# LOW_CURR_MOS.net
KiCad netlist of a schematic drawn in Altium Designer
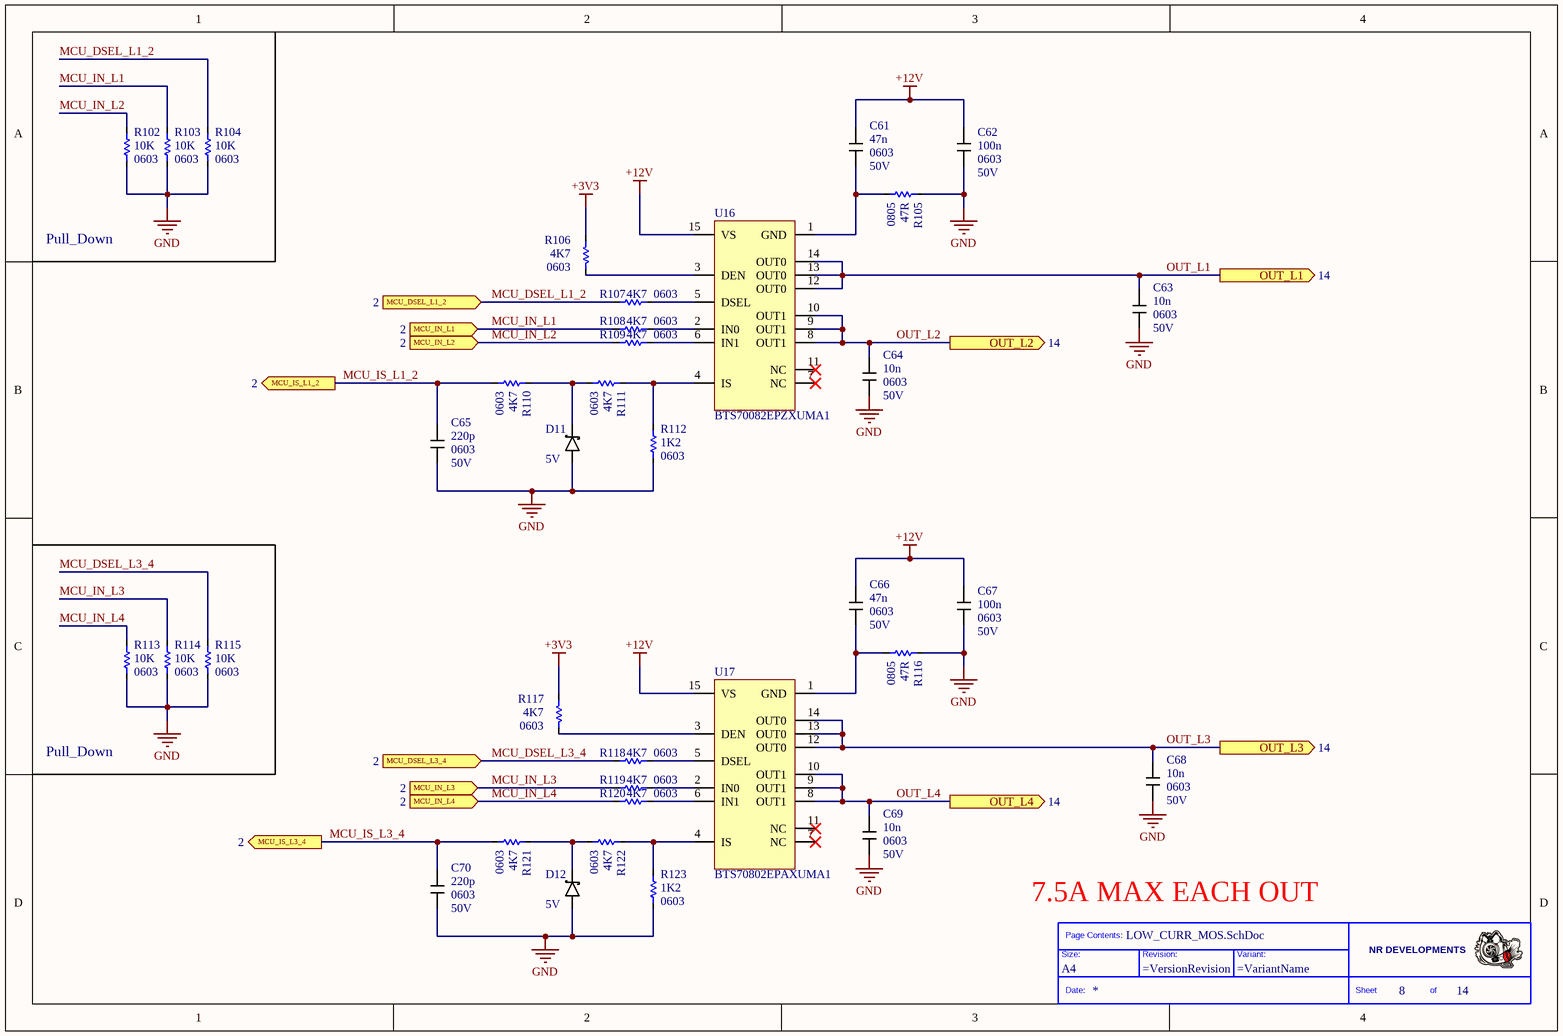
[diagram p0: LOW_CURR_MOS.SchDoc]

(export (version "E")
  (design (tool "Eeschema 10.0.6"))
  (components
    (comp (ref "C61")
      (value "47n")
      (footprint "CAPC1608X09M")
      (fields
        (field (name "MANUFACTURER") "KEMET")
        (field (name "PARTNUMBER") "C0603C473M5RACTU")
        (field (name "CASE") "0603")
        (field (name "VOLTAGE") "50V")
        (field (name "Comment") "CAP")
      )
      (libsource (lib "My_LIB") (part "CAP"))
    )
    (comp (ref "C62")
      (value "100n")
      (footprint "CAPC1608X09M")
      (fields
        (field (name "CASE") "0603")
        (field (name "VOLTAGE") "50V")
        (field (name "MANUFACTURER") "KEMET")
        (field (name "PARTNUMBER") "C0603C104K5RACTU")
        (field (name "Comment") "CAP")
      )
      (libsource (lib "My_LIB") (part "CAP"))
    )
    (comp (ref "C63")
      (value "10n")
      (footprint "CAPC1608X09M")
      (fields
        (field (name "MANUFACTURER") "KEMET")
        (field (name "PARTNUMBER") "C0603C103M5RACTM")
        (field (name "CASE") "0603")
        (field (name "VOLTAGE") "50V")
        (field (name "Comment") "CAP")
      )
      (libsource (lib "My_LIB") (part "CAP"))
    )
    (comp (ref "C64")
      (value "10n")
      (footprint "CAPC1608X09M")
      (fields
        (field (name "MANUFACTURER") "KEMET")
        (field (name "PARTNUMBER") "C0603C103M5RACTM")
        (field (name "CASE") "0603")
        (field (name "VOLTAGE") "50V")
        (field (name "Comment") "CAP")
      )
      (libsource (lib "My_LIB") (part "CAP"))
    )
    (comp (ref "C65")
      (value "220p")
      (footprint "CAPC1608X09M")
      (fields
        (field (name "MANUFACTURER") "KEMET")
        (field (name "PARTNUMBER") "C0603C221J5RACTU")
        (field (name "CASE") "0603")
        (field (name "VOLTAGE") "50V")
        (field (name "Comment") "CAP")
      )
      (libsource (lib "My_LIB") (part "CAP"))
    )
    (comp (ref "C66")
      (value "47n")
      (footprint "CAPC1608X09M")
      (fields
        (field (name "MANUFACTURER") "KEMET")
        (field (name "PARTNUMBER") "C0603C473M5RACTU")
        (field (name "CASE") "0603")
        (field (name "VOLTAGE") "50V")
        (field (name "Comment") "CAP")
      )
      (libsource (lib "My_LIB") (part "CAP"))
    )
    (comp (ref "C67")
      (value "100n")
      (footprint "CAPC1608X09M")
      (fields
        (field (name "CASE") "0603")
        (field (name "VOLTAGE") "50V")
        (field (name "MANUFACTURER") "KEMET")
        (field (name "PARTNUMBER") "C0603C104K5RACTU")
        (field (name "Comment") "CAP")
      )
      (libsource (lib "My_LIB") (part "CAP"))
    )
    (comp (ref "C68")
      (value "10n")
      (footprint "CAPC1608X09M")
      (fields
        (field (name "MANUFACTURER") "KEMET")
        (field (name "PARTNUMBER") "C0603C103M5RACTM")
        (field (name "CASE") "0603")
        (field (name "VOLTAGE") "50V")
        (field (name "Comment") "CAP")
      )
      (libsource (lib "My_LIB") (part "CAP"))
    )
    (comp (ref "C69")
      (value "10n")
      (footprint "CAPC1608X09M")
      (fields
        (field (name "MANUFACTURER") "KEMET")
        (field (name "PARTNUMBER") "C0603C103M5RACTM")
        (field (name "CASE") "0603")
        (field (name "VOLTAGE") "50V")
        (field (name "Comment") "CAP")
      )
      (libsource (lib "My_LIB") (part "CAP"))
    )
    (comp (ref "C70")
      (value "220p")
      (footprint "CAPC1608X09M")
      (fields
        (field (name "MANUFACTURER") "KEMET")
        (field (name "PARTNUMBER") "C0603C221J5RACTU")
        (field (name "CASE") "0603")
        (field (name "VOLTAGE") "50V")
        (field (name "Comment") "CAP")
      )
      (libsource (lib "My_LIB") (part "CAP"))
    )
    (comp (ref "D11")
      (value "5V")
      (footprint "SOT65P210X100-3N - AC")
      (fields
        (field (name "MANUFACTURER") "Nexperia")
        (field (name "PARTNUMBER") "BZX84W-C4V7-QX")
        (field (name "Comment") "Diode_Schottky")
      )
      (libsource (lib "My_LIB") (part "Diode_Schottky"))
    )
    (comp (ref "D12")
      (value "5V")
      (footprint "SOT65P210X100-3N - AC")
      (fields
        (field (name "MANUFACTURER") "Nexperia")
        (field (name "PARTNUMBER") "BZX84W-C4V7-QX")
        (field (name "Comment") "Diode_Schottky")
      )
      (libsource (lib "My_LIB") (part "Diode_Schottky"))
    )
    (comp (ref "R102")
      (value "10K")
      (footprint "RESC1608X06M")
      (fields
        (field (name "CASE") "0603")
        (field (name "MANUFACTURER") "YAGEO")
        (field (name "PARTNUMBER") "AC0603FR-0710KL")
        (field (name "Comment") "Res")
      )
      (libsource (lib "My_LIB") (part "Resistor"))
    )
    (comp (ref "R103")
      (value "10K")
      (footprint "RESC1608X06M")
      (fields
        (field (name "CASE") "0603")
        (field (name "MANUFACTURER") "YAGEO")
        (field (name "PARTNUMBER") "AC0603FR-0710KL")
        (field (name "Comment") "Res")
      )
      (libsource (lib "My_LIB") (part "Resistor"))
    )
    (comp (ref "R104")
      (value "10K")
      (footprint "RESC1608X06M")
      (fields
        (field (name "CASE") "0603")
        (field (name "MANUFACTURER") "YAGEO")
        (field (name "PARTNUMBER") "AC0603FR-0710KL")
        (field (name "Comment") "Res")
      )
      (libsource (lib "My_LIB") (part "Resistor"))
    )
    (comp (ref "R105")
      (value "47R")
      (footprint "RESC2012X06N")
      (fields
        (field (name "MANUFACTURER") "Vishay")
        (field (name "CASE") "0805")
        (field (name "PARTNUMBER") "CRCW080547R0FKEA")
        (field (name "Comment") "Res")
      )
      (libsource (lib "My_LIB") (part "Resistor"))
    )
    (comp (ref "R106")
      (value "4K7")
      (footprint "RESC1608X06M")
      (fields
        (field (name "CASE") "0603")
        (field (name "MANUFACTURER") "YAGEO")
        (field (name "PARTNUMBER") " RC0603FR-074K7L")
        (field (name "Comment") "Res")
      )
      (libsource (lib "My_LIB") (part "Resistor"))
    )
    (comp (ref "R107")
      (value "4K7")
      (footprint "RESC1608X06M")
      (fields
        (field (name "MANUFACTURER") "YAGEO")
        (field (name "CASE") "0603")
        (field (name "PARTNUMBER") " RC0603FR-074K7L")
        (field (name "Comment") "Res")
      )
      (libsource (lib "My_LIB") (part "Resistor"))
    )
    (comp (ref "R108")
      (value "4K7")
      (footprint "RESC1608X06M")
      (fields
        (field (name "MANUFACTURER") "YAGEO")
        (field (name "CASE") "0603")
        (field (name "PARTNUMBER") " RC0603FR-074K7L")
        (field (name "Comment") "Res")
      )
      (libsource (lib "My_LIB") (part "Resistor"))
    )
    (comp (ref "R109")
      (value "4K7")
      (footprint "RESC1608X06M")
      (fields
        (field (name "MANUFACTURER") "YAGEO")
        (field (name "CASE") "0603")
        (field (name "PARTNUMBER") " RC0603FR-074K7L")
        (field (name "Comment") "Res")
      )
      (libsource (lib "My_LIB") (part "Resistor"))
    )
    (comp (ref "R110")
      (value "4K7")
      (footprint "RESC1608X06M")
      (fields
        (field (name "MANUFACTURER") "YAGEO")
        (field (name "CASE") "0603")
        (field (name "PARTNUMBER") " RC0603FR-074K7L")
        (field (name "Comment") "Res")
      )
      (libsource (lib "My_LIB") (part "Resistor"))
    )
    (comp (ref "R111")
      (value "4K7")
      (footprint "RESC1608X06M")
      (fields
        (field (name "MANUFACTURER") "YAGEO")
        (field (name "CASE") "0603")
        (field (name "PARTNUMBER") " RC0603FR-074K7L")
        (field (name "Comment") "Res")
      )
      (libsource (lib "My_LIB") (part "Resistor"))
    )
    (comp (ref "R112")
      (value "1K2")
      (footprint "RESC1608X06M")
      (fields
        (field (name "MANUFACTURER") "Vishay")
        (field (name "CASE") "0603")
        (field (name "PARTNUMBER") "CRCW06031K20FKEA")
        (field (name "Comment") "Res")
      )
      (libsource (lib "My_LIB") (part "Resistor"))
    )
    (comp (ref "R113")
      (value "10K")
      (footprint "RESC1608X06M")
      (fields
        (field (name "CASE") "0603")
        (field (name "MANUFACTURER") "YAGEO")
        (field (name "PARTNUMBER") "AC0603FR-0710KL")
        (field (name "Comment") "Res")
      )
      (libsource (lib "My_LIB") (part "Resistor"))
    )
    (comp (ref "R114")
      (value "10K")
      (footprint "RESC1608X06M")
      (fields
        (field (name "CASE") "0603")
        (field (name "MANUFACTURER") "YAGEO")
        (field (name "PARTNUMBER") "AC0603FR-0710KL")
        (field (name "Comment") "Res")
      )
      (libsource (lib "My_LIB") (part "Resistor"))
    )
    (comp (ref "R115")
      (value "10K")
      (footprint "RESC1608X06M")
      (fields
        (field (name "CASE") "0603")
        (field (name "MANUFACTURER") "YAGEO")
        (field (name "PARTNUMBER") "AC0603FR-0710KL")
        (field (name "Comment") "Res")
      )
      (libsource (lib "My_LIB") (part "Resistor"))
    )
    (comp (ref "R116")
      (value "47R")
      (footprint "RESC2012X06N")
      (fields
        (field (name "MANUFACTURER") "Vishay")
        (field (name "CASE") "0805")
        (field (name "PARTNUMBER") "CRCW080547R0FKEA")
        (field (name "Comment") "Res")
      )
      (libsource (lib "My_LIB") (part "Resistor"))
    )
    (comp (ref "R117")
      (value "4K7")
      (footprint "RESC1608X06M")
      (fields
        (field (name "CASE") "0603")
        (field (name "MANUFACTURER") "YAGEO")
        (field (name "PARTNUMBER") " RC0603FR-074K7L")
        (field (name "Comment") "Res")
      )
      (libsource (lib "My_LIB") (part "Resistor"))
    )
    (comp (ref "R118")
      (value "4K7")
      (footprint "RESC1608X06M")
      (fields
        (field (name "MANUFACTURER") "YAGEO")
        (field (name "CASE") "0603")
        (field (name "PARTNUMBER") " RC0603FR-074K7L")
        (field (name "Comment") "Res")
      )
      (libsource (lib "My_LIB") (part "Resistor"))
    )
    (comp (ref "R119")
      (value "4K7")
      (footprint "RESC1608X06M")
      (fields
        (field (name "MANUFACTURER") "YAGEO")
        (field (name "CASE") "0603")
        (field (name "PARTNUMBER") " RC0603FR-074K7L")
        (field (name "Comment") "Res")
      )
      (libsource (lib "My_LIB") (part "Resistor"))
    )
    (comp (ref "R120")
      (value "4K7")
      (footprint "RESC1608X06M")
      (fields
        (field (name "MANUFACTURER") "YAGEO")
        (field (name "CASE") "0603")
        (field (name "PARTNUMBER") " RC0603FR-074K7L")
        (field (name "Comment") "Res")
      )
      (libsource (lib "My_LIB") (part "Resistor"))
    )
    (comp (ref "R121")
      (value "4K7")
      (footprint "RESC1608X06M")
      (fields
        (field (name "MANUFACTURER") "YAGEO")
        (field (name "CASE") "0603")
        (field (name "PARTNUMBER") " RC0603FR-074K7L")
        (field (name "Comment") "Res")
      )
      (libsource (lib "My_LIB") (part "Resistor"))
    )
    (comp (ref "R122")
      (value "4K7")
      (footprint "RESC1608X06M")
      (fields
        (field (name "MANUFACTURER") "YAGEO")
        (field (name "CASE") "0603")
        (field (name "PARTNUMBER") " RC0603FR-074K7L")
        (field (name "Comment") "Res")
      )
      (libsource (lib "My_LIB") (part "Resistor"))
    )
    (comp (ref "R123")
      (value "1K2")
      (footprint "RESC1608X06M")
      (fields
        (field (name "MANUFACTURER") "Vishay")
        (field (name "CASE") "0603")
        (field (name "PARTNUMBER") "CRCW06031K20FKEA")
        (field (name "Comment") "Res")
      )
      (libsource (lib "My_LIB") (part "Resistor"))
    )
    (comp (ref "U16")
      (value "BTS70082EPZXUMA1")
      (footprint "SOP65P600X115-15")
      (description "Smart High-Side Power Switch 7.5A")
      (fields (field (name "MANUFACTURER") "Infineon Technologies"))
      (libsource (lib "My_LIB") (part "BTS70082EPZXUMA1"))
    )
    (comp (ref "U17")
      (value "BTS70802EPAXUMA1")
      (footprint "SOP65P600X115-15")
      (description "Smart High-Side Power Switch 3A")
      (fields (field (name "MANUFACTURER") "Infineon Technologies"))
      (libsource (lib "My_LIB") (part "BTS70802EPAXUMA1"))
    )
  )
  (nets
    (net (code "1") (name "+3V3") (class "Default")
      (node (ref "R106") (pin "2") (pinfunction "2_2") (pintype "passive"))
      (node (ref "R117") (pin "2") (pinfunction "2_2") (pintype "passive"))
    )
    (net (code "2") (name "+12V") (class "Default")
      (node (ref "C61") (pin "1") (pinfunction "1_1") (pintype "passive"))
      (node (ref "C62") (pin "1") (pinfunction "1_1") (pintype "passive"))
      (node (ref "C66") (pin "1") (pinfunction "1_1") (pintype "passive"))
      (node (ref "C67") (pin "1") (pinfunction "1_1") (pintype "passive"))
      (node (ref "U16") (pin "15") (pinfunction "VS_15") (pintype "power_in"))
      (node (ref "U17") (pin "15") (pinfunction "VS_15") (pintype "power_in"))
    )
    (net (code "3") (name "/MCU_DSEL_L1_2") (class "Default")
      (node (ref "R104") (pin "2") (pinfunction "2_2") (pintype "passive"))
      (node (ref "R107") (pin "1") (pinfunction "1_1") (pintype "passive"))
    )
    (net (code "4") (name "/MCU_DSEL_L3_4") (class "Default")
      (node (ref "R115") (pin "2") (pinfunction "2_2") (pintype "passive"))
      (node (ref "R118") (pin "1") (pinfunction "1_1") (pintype "passive"))
    )
    (net (code "5") (name "/MCU_IN_L1") (class "Default")
      (node (ref "R103") (pin "2") (pinfunction "2_2") (pintype "passive"))
      (node (ref "R108") (pin "1") (pinfunction "1_1") (pintype "passive"))
    )
    (net (code "6") (name "/MCU_IN_L2") (class "Default")
      (node (ref "R102") (pin "2") (pinfunction "2_2") (pintype "passive"))
      (node (ref "R109") (pin "1") (pinfunction "1_1") (pintype "passive"))
    )
    (net (code "7") (name "/MCU_IN_L3") (class "Default")
      (node (ref "R114") (pin "2") (pinfunction "2_2") (pintype "passive"))
      (node (ref "R119") (pin "1") (pinfunction "1_1") (pintype "passive"))
    )
    (net (code "8") (name "/MCU_IN_L4") (class "Default")
      (node (ref "R113") (pin "2") (pinfunction "2_2") (pintype "passive"))
      (node (ref "R120") (pin "1") (pinfunction "1_1") (pintype "passive"))
    )
    (net (code "9") (name "/MCU_IS_L1_2") (class "Default")
      (node (ref "C65") (pin "1") (pinfunction "1_1") (pintype "passive"))
      (node (ref "R110") (pin "1") (pinfunction "1_1") (pintype "passive"))
    )
    (net (code "10") (name "/MCU_IS_L3_4") (class "Default")
      (node (ref "C70") (pin "1") (pinfunction "1_1") (pintype "passive"))
      (node (ref "R121") (pin "1") (pinfunction "1_1") (pintype "passive"))
    )
    (net (code "11") (name "/OUT_L1") (class "Default")
      (node (ref "C63") (pin "1") (pinfunction "1_1") (pintype "passive"))
      (node (ref "U16") (pin "12") (pinfunction "OUT0_12") (pintype "passive"))
      (node (ref "U16") (pin "13") (pinfunction "OUT0_13") (pintype "passive"))
      (node (ref "U16") (pin "14") (pinfunction "OUT0_14") (pintype "passive"))
    )
    (net (code "12") (name "/OUT_L2") (class "Default")
      (node (ref "C64") (pin "1") (pinfunction "1_1") (pintype "passive"))
      (node (ref "U16") (pin "10") (pinfunction "OUT1_10") (pintype "passive"))
      (node (ref "U16") (pin "8") (pinfunction "OUT1_8") (pintype "passive"))
      (node (ref "U16") (pin "9") (pinfunction "OUT1_9") (pintype "passive"))
    )
    (net (code "13") (name "/OUT_L3") (class "Default")
      (node (ref "C68") (pin "1") (pinfunction "1_1") (pintype "passive"))
      (node (ref "U17") (pin "12") (pinfunction "OUT0_12") (pintype "passive"))
      (node (ref "U17") (pin "13") (pinfunction "OUT0_13") (pintype "passive"))
      (node (ref "U17") (pin "14") (pinfunction "OUT0_14") (pintype "passive"))
    )
    (net (code "14") (name "/OUT_L4") (class "Default")
      (node (ref "C69") (pin "1") (pinfunction "1_1") (pintype "passive"))
      (node (ref "U17") (pin "10") (pinfunction "OUT1_10") (pintype "passive"))
      (node (ref "U17") (pin "8") (pinfunction "OUT1_8") (pintype "passive"))
      (node (ref "U17") (pin "9") (pinfunction "OUT1_9") (pintype "passive"))
    )
    (net (code "15") (name "GND") (class "Default")
      (node (ref "C62") (pin "2") (pinfunction "2_2") (pintype "passive"))
      (node (ref "C63") (pin "2") (pinfunction "2_2") (pintype "passive"))
      (node (ref "C64") (pin "2") (pinfunction "2_2") (pintype "passive"))
      (node (ref "C65") (pin "2") (pinfunction "2_2") (pintype "passive"))
      (node (ref "C67") (pin "2") (pinfunction "2_2") (pintype "passive"))
      (node (ref "C68") (pin "2") (pinfunction "2_2") (pintype "passive"))
      (node (ref "C69") (pin "2") (pinfunction "2_2") (pintype "passive"))
      (node (ref "C70") (pin "2") (pinfunction "2_2") (pintype "passive"))
      (node (ref "D11") (pin "A") (pinfunction "A_A") (pintype "passive"))
      (node (ref "D12") (pin "A") (pinfunction "A_A") (pintype "passive"))
      (node (ref "R102") (pin "1") (pinfunction "1_1") (pintype "passive"))
      (node (ref "R103") (pin "1") (pinfunction "1_1") (pintype "passive"))
      (node (ref "R104") (pin "1") (pinfunction "1_1") (pintype "passive"))
      (node (ref "R105") (pin "2") (pinfunction "2_2") (pintype "passive"))
      (node (ref "R112") (pin "1") (pinfunction "1_1") (pintype "passive"))
      (node (ref "R113") (pin "1") (pinfunction "1_1") (pintype "passive"))
      (node (ref "R114") (pin "1") (pinfunction "1_1") (pintype "passive"))
      (node (ref "R115") (pin "1") (pinfunction "1_1") (pintype "passive"))
      (node (ref "R116") (pin "2") (pinfunction "2_2") (pintype "passive"))
      (node (ref "R123") (pin "1") (pinfunction "1_1") (pintype "passive"))
    )
    (net (code "16") (name "Net-(D11-PadC)") (class "Default")
      (node (ref "D11") (pin "C") (pinfunction "C_C") (pintype "passive"))
      (node (ref "R110") (pin "2") (pinfunction "2_2") (pintype "passive"))
      (node (ref "R111") (pin "1") (pinfunction "1_1") (pintype "passive"))
    )
    (net (code "17") (name "Net-(D12-PadC)") (class "Default")
      (node (ref "D12") (pin "C") (pinfunction "C_C") (pintype "passive"))
      (node (ref "R121") (pin "2") (pinfunction "2_2") (pintype "passive"))
      (node (ref "R122") (pin "1") (pinfunction "1_1") (pintype "passive"))
    )
    (net (code "18") (name "Net-(U16-DEN)") (class "Default")
      (node (ref "R106") (pin "1") (pinfunction "1_1") (pintype "passive"))
      (node (ref "U16") (pin "3") (pinfunction "DEN_3") (pintype "passive"))
    )
    (net (code "19") (name "Net-(U16-DSEL)") (class "Default")
      (node (ref "R107") (pin "2") (pinfunction "2_2") (pintype "passive"))
      (node (ref "U16") (pin "5") (pinfunction "DSEL_5") (pintype "passive"))
    )
    (net (code "20") (name "Net-(U16-GND)") (class "Default")
      (node (ref "C61") (pin "2") (pinfunction "2_2") (pintype "passive"))
      (node (ref "R105") (pin "1") (pinfunction "1_1") (pintype "passive"))
      (node (ref "U16") (pin "1") (pinfunction "GND_1") (pintype "power_in"))
    )
    (net (code "21") (name "Net-(U16-IN0)") (class "Default")
      (node (ref "R108") (pin "2") (pinfunction "2_2") (pintype "passive"))
      (node (ref "U16") (pin "2") (pinfunction "IN0_2") (pintype "passive"))
    )
    (net (code "22") (name "Net-(U16-IN1)") (class "Default")
      (node (ref "R109") (pin "2") (pinfunction "2_2") (pintype "passive"))
      (node (ref "U16") (pin "6") (pinfunction "IN1_6") (pintype "passive"))
    )
    (net (code "23") (name "Net-(U16-IS)") (class "Default")
      (node (ref "R111") (pin "2") (pinfunction "2_2") (pintype "passive"))
      (node (ref "R112") (pin "2") (pinfunction "2_2") (pintype "passive"))
      (node (ref "U16") (pin "4") (pinfunction "IS_4") (pintype "passive"))
    )
    (net (code "24") (name "Net-(U17-DEN)") (class "Default")
      (node (ref "R117") (pin "1") (pinfunction "1_1") (pintype "passive"))
      (node (ref "U17") (pin "3") (pinfunction "DEN_3") (pintype "passive"))
    )
    (net (code "25") (name "Net-(U17-DSEL)") (class "Default")
      (node (ref "R118") (pin "2") (pinfunction "2_2") (pintype "passive"))
      (node (ref "U17") (pin "5") (pinfunction "DSEL_5") (pintype "passive"))
    )
    (net (code "26") (name "Net-(U17-GND)") (class "Default")
      (node (ref "C66") (pin "2") (pinfunction "2_2") (pintype "passive"))
      (node (ref "R116") (pin "1") (pinfunction "1_1") (pintype "passive"))
      (node (ref "U17") (pin "1") (pinfunction "GND_1") (pintype "power_in"))
    )
    (net (code "27") (name "Net-(U17-IN0)") (class "Default")
      (node (ref "R119") (pin "2") (pinfunction "2_2") (pintype "passive"))
      (node (ref "U17") (pin "2") (pinfunction "IN0_2") (pintype "passive"))
    )
    (net (code "28") (name "Net-(U17-IN1)") (class "Default")
      (node (ref "R120") (pin "2") (pinfunction "2_2") (pintype "passive"))
      (node (ref "U17") (pin "6") (pinfunction "IN1_6") (pintype "passive"))
    )
    (net (code "29") (name "Net-(U17-IS)") (class "Default")
      (node (ref "R122") (pin "2") (pinfunction "2_2") (pintype "passive"))
      (node (ref "R123") (pin "2") (pinfunction "2_2") (pintype "passive"))
      (node (ref "U17") (pin "4") (pinfunction "IS_4") (pintype "passive"))
    )
    (net (code "30") (name "unconnected-(U16-NC-Pad7)") (class "Default")
      (node (ref "U16") (pin "7") (pinfunction "NC_7") (pintype "passive+no_connect"))
    )
    (net (code "31") (name "unconnected-(U16-NC-Pad11)") (class "Default")
      (node (ref "U16") (pin "11") (pinfunction "NC_11") (pintype "passive+no_connect"))
    )
    (net (code "32") (name "unconnected-(U17-NC-Pad7)") (class "Default")
      (node (ref "U17") (pin "7") (pinfunction "NC_7") (pintype "passive+no_connect"))
    )
    (net (code "33") (name "unconnected-(U17-NC-Pad11)") (class "Default")
      (node (ref "U17") (pin "11") (pinfunction "NC_11") (pintype "passive+no_connect"))
    )
  )
)
